# AlimSoloBatterie.net
KiCad netlist of a schematic drawn in EAGLE
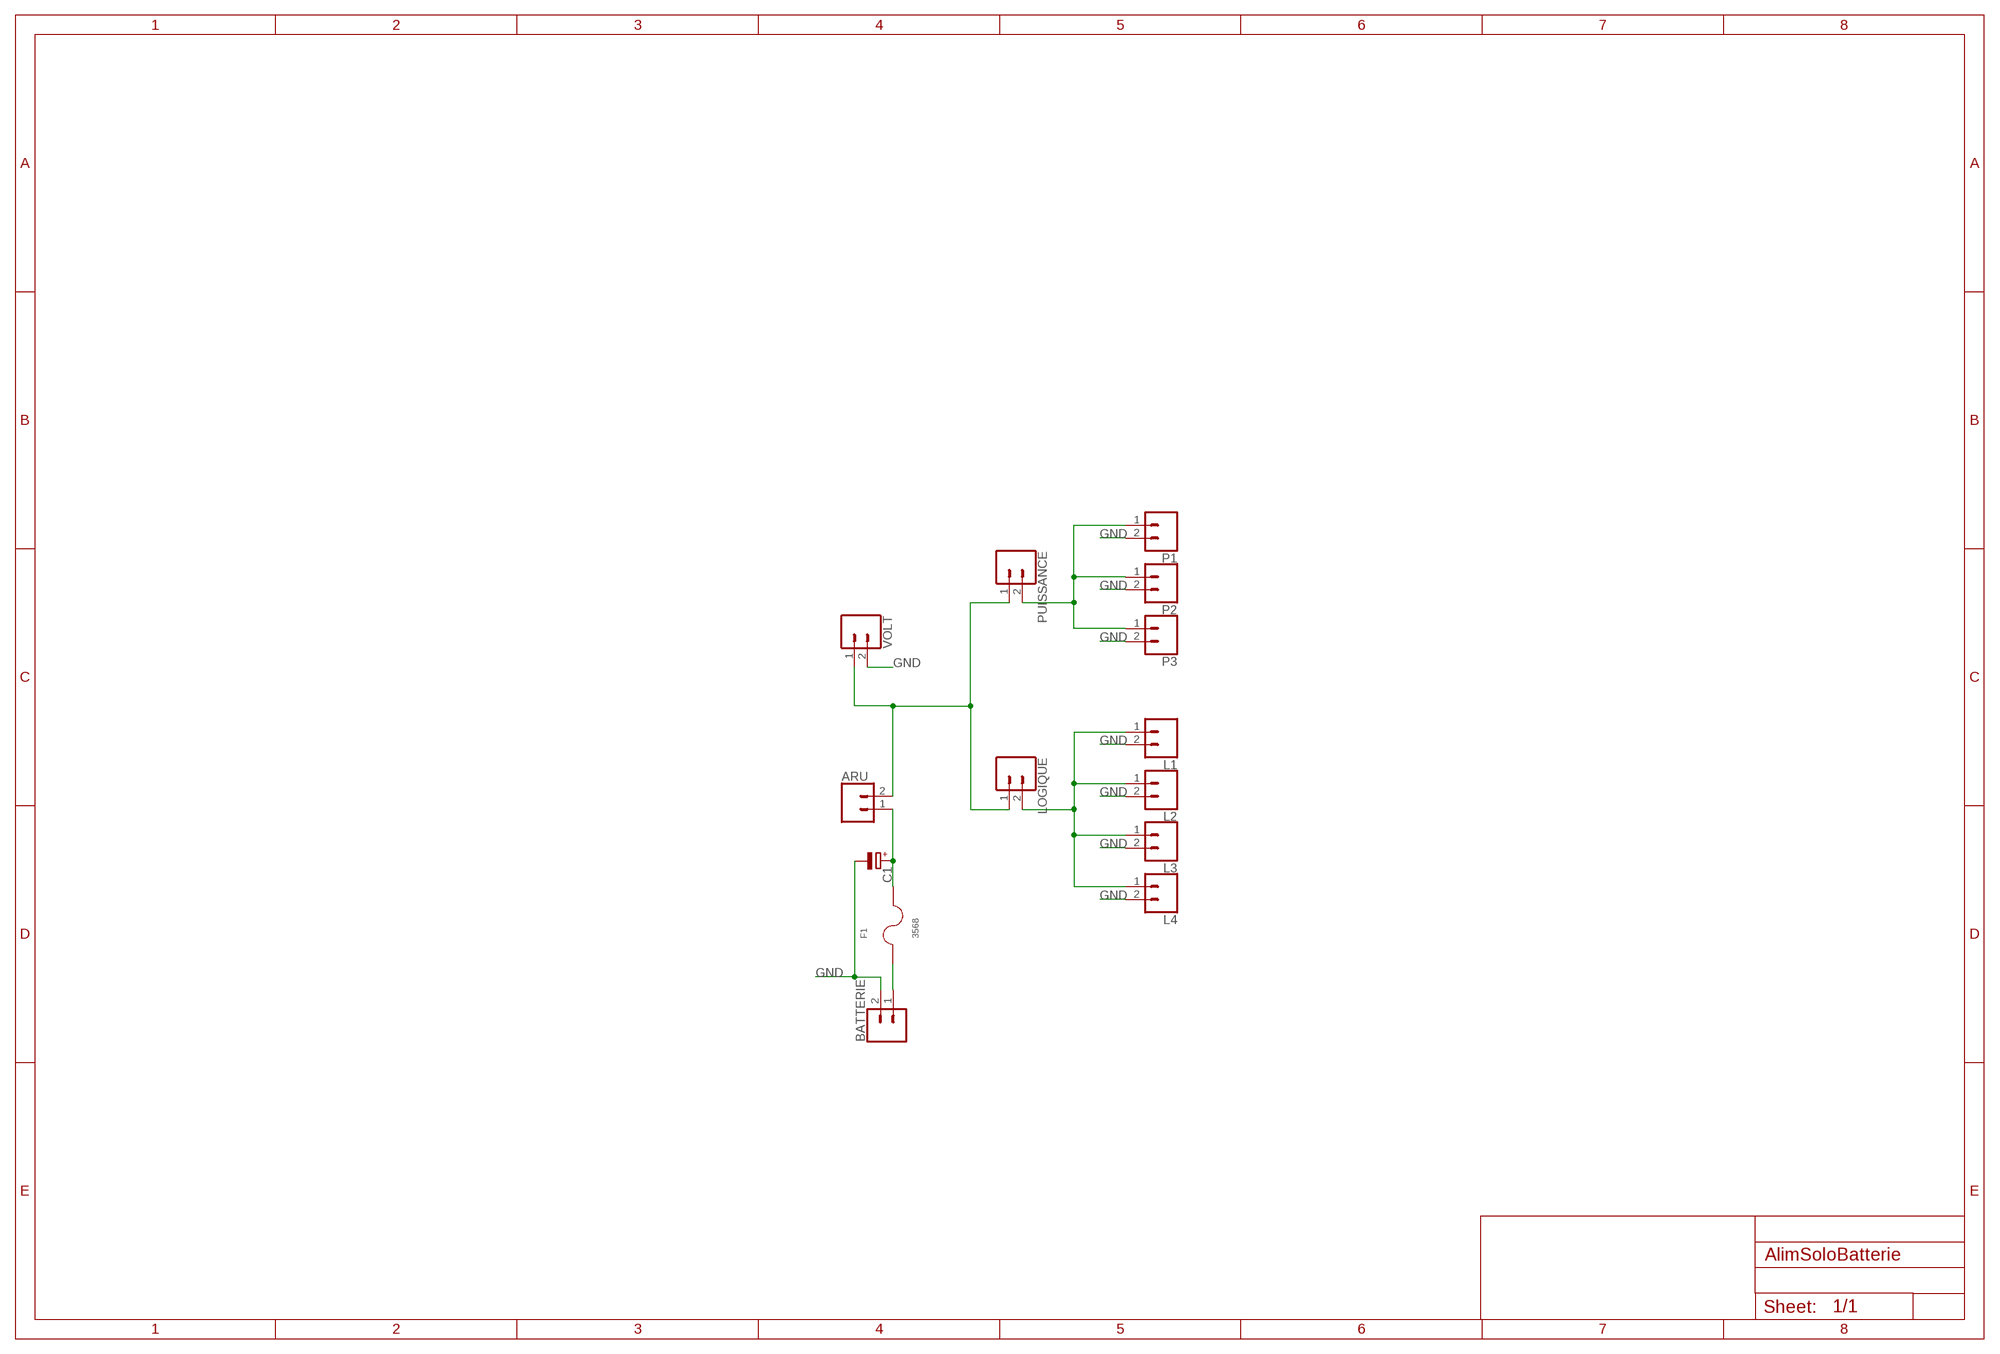
[diagram p0: schematic, sheet 1]

(export (version "E")
  (design (tool "Eeschema 10.0.6"))
  (components
    (comp (ref "ARU")
      (value "CONN_02POLAR")
      (footprint "eagle-import:MOLEX-1X2")
      (libsource (lib "eagle-import") (part "CONN_02POLAR"))
    )
    (comp (ref "BATTERIE")
      (value "CONN_02POLAR")
      (footprint "eagle-import:MOLEX-1X2")
      (libsource (lib "eagle-import") (part "CONN_02POLAR"))
    )
    (comp (ref "C1")
      (value "CPOL-EUE5-13")
      (footprint "eagle-import:E5-13")
      (libsource (lib "eagle-import") (part "CPOL-EUE5-13"))
    )
    (comp (ref "F1")
      (value "3568")
      (footprint "eagle-import:FUSE_3568")
      (fields (field (name "MF") "Keystone Electronics"))
      (libsource (lib "eagle-import") (part "3568"))
    )
    (comp (ref "L1")
      (value "CONN_02POLAR")
      (footprint "eagle-import:MOLEX-1X2")
      (libsource (lib "eagle-import") (part "CONN_02POLAR"))
    )
    (comp (ref "L2")
      (value "CONN_02POLAR")
      (footprint "eagle-import:MOLEX-1X2")
      (libsource (lib "eagle-import") (part "CONN_02POLAR"))
    )
    (comp (ref "L3")
      (value "CONN_02POLAR")
      (footprint "eagle-import:MOLEX-1X2")
      (libsource (lib "eagle-import") (part "CONN_02POLAR"))
    )
    (comp (ref "L4")
      (value "CONN_02POLAR")
      (footprint "eagle-import:MOLEX-1X2")
      (libsource (lib "eagle-import") (part "CONN_02POLAR"))
    )
    (comp (ref "LOGIQUE")
      (value "CONN_02POLAR")
      (footprint "eagle-import:MOLEX-1X2")
      (libsource (lib "eagle-import") (part "CONN_02POLAR"))
    )
    (comp (ref "P1")
      (value "CONN_02POLAR")
      (footprint "eagle-import:MOLEX-1X2")
      (libsource (lib "eagle-import") (part "CONN_02POLAR"))
    )
    (comp (ref "P2")
      (value "CONN_02POLAR")
      (footprint "eagle-import:MOLEX-1X2")
      (libsource (lib "eagle-import") (part "CONN_02POLAR"))
    )
    (comp (ref "P3")
      (value "CONN_02POLAR")
      (footprint "eagle-import:MOLEX-1X2")
      (libsource (lib "eagle-import") (part "CONN_02POLAR"))
    )
    (comp (ref "PUISSANCE")
      (value "CONN_02POLAR")
      (footprint "eagle-import:MOLEX-1X2")
      (libsource (lib "eagle-import") (part "CONN_02POLAR"))
    )
    (comp (ref "VOLT")
      (value "CONN_02POLAR")
      (footprint "eagle-import:MOLEX-1X2")
      (libsource (lib "eagle-import") (part "CONN_02POLAR"))
    )
  )
  (nets
    (net (code "1") (name "/GND") (class "Default")
      (node (ref "BATTERIE") (pin "2") (pinfunction "2_2") (pintype "passive"))
      (node (ref "C1") (pin "-") (pinfunction "-_-") (pintype "passive"))
      (node (ref "L1") (pin "2") (pinfunction "2_2") (pintype "passive"))
      (node (ref "L2") (pin "2") (pinfunction "2_2") (pintype "passive"))
      (node (ref "L3") (pin "2") (pinfunction "2_2") (pintype "passive"))
      (node (ref "L4") (pin "2") (pinfunction "2_2") (pintype "passive"))
      (node (ref "P1") (pin "2") (pinfunction "2_2") (pintype "passive"))
      (node (ref "P2") (pin "2") (pinfunction "2_2") (pintype "passive"))
      (node (ref "P3") (pin "2") (pinfunction "2_2") (pintype "passive"))
      (node (ref "VOLT") (pin "2") (pinfunction "2_2") (pintype "passive"))
    )
    (net (code "2") (name "Net-(ARU-Pad1)") (class "Default")
      (node (ref "ARU") (pin "1") (pinfunction "1_1") (pintype "passive"))
      (node (ref "C1") (pin "+") (pinfunction "+_+") (pintype "passive"))
      (node (ref "F1") (pin "2") (pinfunction "2_2") (pintype "passive"))
      (node (ref "F1") (pin "4") (pinfunction "2_4") (pintype "passive"))
    )
    (net (code "3") (name "Net-(ARU-Pad2)") (class "Default")
      (node (ref "ARU") (pin "2") (pinfunction "2_2") (pintype "passive"))
      (node (ref "LOGIQUE") (pin "1") (pinfunction "1_1") (pintype "passive"))
      (node (ref "PUISSANCE") (pin "1") (pinfunction "1_1") (pintype "passive"))
      (node (ref "VOLT") (pin "1") (pinfunction "1_1") (pintype "passive"))
    )
    (net (code "4") (name "Net-(BATTERIE-Pad1)") (class "Default")
      (node (ref "BATTERIE") (pin "1") (pinfunction "1_1") (pintype "passive"))
      (node (ref "F1") (pin "1") (pinfunction "1_1") (pintype "passive"))
      (node (ref "F1") (pin "3") (pinfunction "1_3") (pintype "passive"))
    )
    (net (code "5") (name "Net-(L1-Pad1)") (class "Default")
      (node (ref "L1") (pin "1") (pinfunction "1_1") (pintype "passive"))
      (node (ref "L2") (pin "1") (pinfunction "1_1") (pintype "passive"))
      (node (ref "L3") (pin "1") (pinfunction "1_1") (pintype "passive"))
      (node (ref "L4") (pin "1") (pinfunction "1_1") (pintype "passive"))
      (node (ref "LOGIQUE") (pin "2") (pinfunction "2_2") (pintype "passive"))
    )
    (net (code "6") (name "Net-(P1-Pad1)") (class "Default")
      (node (ref "P1") (pin "1") (pinfunction "1_1") (pintype "passive"))
      (node (ref "P2") (pin "1") (pinfunction "1_1") (pintype "passive"))
      (node (ref "P3") (pin "1") (pinfunction "1_1") (pintype "passive"))
      (node (ref "PUISSANCE") (pin "2") (pinfunction "2_2") (pintype "passive"))
    )
  )
)
